# Ariel_v6_2.net
KiCad netlist of a schematic drawn in EAGLE
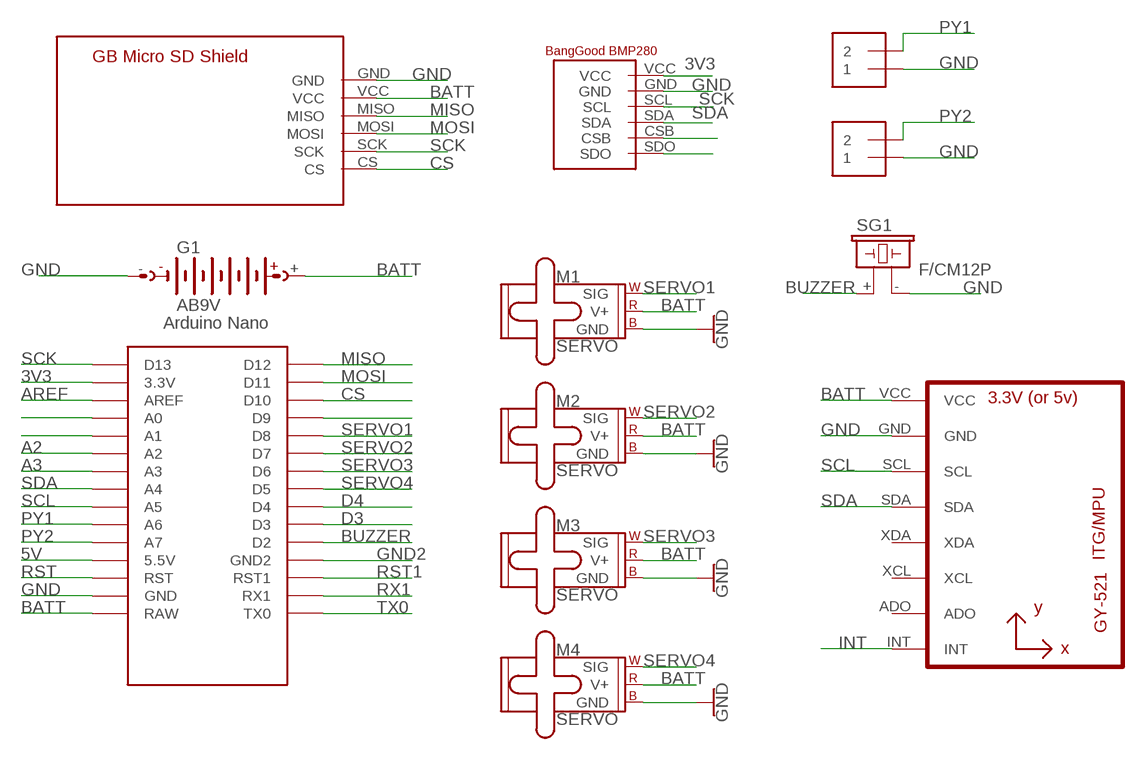
[diagram p0: schematic, sheet 1]

(export (version "E")
  (design (tool "Eeschema 10.0.6"))
  (components
    (comp (ref "G1")
      (value "AB9V")
      (footprint "eagle-import:AB9V")
      (libsource (lib "eagle-import") (part "AB9V"))
    )
    (comp (ref "J1")
      (value "1X2-3.5MM")
      (footprint "eagle-import:1X2-3.5MM")
      (libsource (lib "eagle-import") (part "1X2-3.5MM"))
    )
    (comp (ref "J2")
      (value "1X2-3.5MM")
      (footprint "eagle-import:1X2-3.5MM")
      (libsource (lib "eagle-import") (part "1X2-3.5MM"))
    )
    (comp (ref "M1")
      (value "SERVO")
      (footprint "eagle-import:1X03")
      (libsource (lib "eagle-import") (part "SERVO"))
    )
    (comp (ref "M2")
      (value "SERVO")
      (footprint "eagle-import:1X03")
      (libsource (lib "eagle-import") (part "SERVO"))
    )
    (comp (ref "M3")
      (value "SERVO")
      (footprint "eagle-import:1X03")
      (libsource (lib "eagle-import") (part "SERVO"))
    )
    (comp (ref "M4")
      (value "SERVO")
      (footprint "eagle-import:1X03")
      (libsource (lib "eagle-import") (part "SERVO"))
    )
    (comp (ref "SG1")
      (value "F/CM12P")
      (footprint "eagle-import:F_CM12P")
      (libsource (lib "eagle-import") (part "F/CM12P"))
    )
    (comp (ref "U$1")
      (value "NANO")
      (footprint "eagle-import:NANO")
      (libsource (lib "eagle-import") (part "NANO"))
    )
    (comp (ref "U$2")
      (value "BG_BMP280")
      (footprint "eagle-import:01BG_BMP280")
      (libsource (lib "eagle-import") (part "BG_BMP280"))
    )
    (comp (ref "U$3")
      (value "GBMICROSDSHIELD")
      (footprint "eagle-import:GBMICROSDSHIELD")
      (libsource (lib "eagle-import") (part "GBMICROSDSHIELD"))
    )
    (comp (ref "U1")
      (value "GY-521MPU6050")
      (footprint "eagle-import:GY-521")
      (libsource (lib "eagle-import") (part "GY-521MPU6050"))
    )
  )
  (nets
    (net (code "1") (name "/3V3") (class "Default")
      (node (ref "U$1") (pin "3.3V") (pinfunction "3.3V_3.3V") (pintype "bidirectional"))
      (node (ref "U$2") (pin "VCC") (pinfunction "VCC_VCC") (pintype "bidirectional"))
    )
    (net (code "2") (name "/5V") (class "Default")
      (node (ref "U$1") (pin "5V") (pinfunction "5.5V_5V") (pintype "bidirectional"))
    )
    (net (code "3") (name "/A2") (class "Default")
      (node (ref "U$1") (pin "A2") (pinfunction "A2_A2") (pintype "bidirectional"))
    )
    (net (code "4") (name "/A3") (class "Default")
      (node (ref "U$1") (pin "A3") (pinfunction "A3_A3") (pintype "bidirectional"))
    )
    (net (code "5") (name "/AREF") (class "Default")
      (node (ref "U$1") (pin "AREF") (pinfunction "AREF_AREF") (pintype "bidirectional"))
    )
    (net (code "6") (name "/BATT") (class "Default")
      (node (ref "G1") (pin "+") (pinfunction "+_+") (pintype "passive"))
      (node (ref "M1") (pin "2") (pinfunction "V+_2") (pintype "bidirectional"))
      (node (ref "M2") (pin "2") (pinfunction "V+_2") (pintype "bidirectional"))
      (node (ref "M3") (pin "2") (pinfunction "V+_2") (pintype "bidirectional"))
      (node (ref "M4") (pin "2") (pinfunction "V+_2") (pintype "bidirectional"))
      (node (ref "U$1") (pin "RAW") (pinfunction "RAW_RAW") (pintype "bidirectional"))
      (node (ref "U$3") (pin "VCC") (pinfunction "VCC_VCC") (pintype "bidirectional"))
      (node (ref "U1") (pin "VCC") (pinfunction "VCC_VCC") (pintype "bidirectional"))
    )
    (net (code "7") (name "/BUZZER") (class "Default")
      (node (ref "SG1") (pin "+") (pinfunction "1_+") (pintype "passive"))
      (node (ref "U$1") (pin "D2") (pinfunction "D2_D2") (pintype "bidirectional"))
    )
    (net (code "8") (name "/CS") (class "Default")
      (node (ref "U$1") (pin "D10") (pinfunction "D10_D10") (pintype "bidirectional"))
      (node (ref "U$3") (pin "CS") (pinfunction "CS_CS") (pintype "bidirectional"))
    )
    (net (code "9") (name "/D3") (class "Default")
      (node (ref "U$1") (pin "D3") (pinfunction "D3_D3") (pintype "bidirectional"))
    )
    (net (code "10") (name "/D4") (class "Default")
      (node (ref "U$1") (pin "D4") (pinfunction "D4_D4") (pintype "bidirectional"))
    )
    (net (code "11") (name "/GND2") (class "Default")
      (node (ref "U$1") (pin "GND1") (pinfunction "GND2_GND1") (pintype "bidirectional"))
    )
    (net (code "12") (name "/INT") (class "Default")
      (node (ref "U1") (pin "INT") (pinfunction "INT_INT") (pintype "bidirectional"))
    )
    (net (code "13") (name "/MISO") (class "Default")
      (node (ref "U$1") (pin "D12") (pinfunction "D12_D12") (pintype "bidirectional"))
      (node (ref "U$3") (pin "MISO") (pinfunction "MISO_MISO") (pintype "bidirectional"))
    )
    (net (code "14") (name "/MOSI") (class "Default")
      (node (ref "U$1") (pin "D11") (pinfunction "D11_D11") (pintype "bidirectional"))
      (node (ref "U$3") (pin "MOSI") (pinfunction "MOSI_MOSI") (pintype "bidirectional"))
    )
    (net (code "15") (name "/PY1") (class "Default")
      (node (ref "J1") (pin "2") (pinfunction "2_2") (pintype "passive"))
      (node (ref "U$1") (pin "A6") (pinfunction "A6_A6") (pintype "bidirectional"))
    )
    (net (code "16") (name "/PY2") (class "Default")
      (node (ref "J2") (pin "2") (pinfunction "2_2") (pintype "passive"))
      (node (ref "U$1") (pin "A7") (pinfunction "A7_A7") (pintype "bidirectional"))
    )
    (net (code "17") (name "/RST") (class "Default")
      (node (ref "U$1") (pin "RST") (pinfunction "RST_RST") (pintype "bidirectional"))
    )
    (net (code "18") (name "/RST1") (class "Default")
      (node (ref "U$1") (pin "RST1") (pinfunction "RST1_RST1") (pintype "bidirectional"))
    )
    (net (code "19") (name "/RX1") (class "Default")
      (node (ref "U$1") (pin "RX1") (pinfunction "RX1_RX1") (pintype "bidirectional"))
    )
    (net (code "20") (name "/SCK") (class "Default")
      (node (ref "U$1") (pin "D13") (pinfunction "D13_D13") (pintype "bidirectional"))
      (node (ref "U$2") (pin "SCL") (pinfunction "SCL_SCL") (pintype "bidirectional"))
      (node (ref "U$3") (pin "SCK") (pinfunction "SCK_SCK") (pintype "bidirectional"))
    )
    (net (code "21") (name "/SCL") (class "Default")
      (node (ref "U$1") (pin "A5") (pinfunction "A5_A5") (pintype "bidirectional"))
      (node (ref "U1") (pin "SCL") (pinfunction "SCL_SCL") (pintype "bidirectional"))
    )
    (net (code "22") (name "/SDA") (class "Default")
      (node (ref "U$1") (pin "A4") (pinfunction "A4_A4") (pintype "bidirectional"))
      (node (ref "U$2") (pin "SDA") (pinfunction "SDA_SDA") (pintype "bidirectional"))
      (node (ref "U1") (pin "SDA") (pinfunction "SDA_SDA") (pintype "bidirectional"))
    )
    (net (code "23") (name "/SERVO1") (class "Default")
      (node (ref "M1") (pin "1") (pinfunction "SIG_1") (pintype "bidirectional"))
      (node (ref "U$1") (pin "D8") (pinfunction "D8_D8") (pintype "bidirectional"))
    )
    (net (code "24") (name "/SERVO2") (class "Default")
      (node (ref "M2") (pin "1") (pinfunction "SIG_1") (pintype "bidirectional"))
      (node (ref "U$1") (pin "D7") (pinfunction "D7_D7") (pintype "bidirectional"))
    )
    (net (code "25") (name "/SERVO3") (class "Default")
      (node (ref "M3") (pin "1") (pinfunction "SIG_1") (pintype "bidirectional"))
      (node (ref "U$1") (pin "D6") (pinfunction "D6_D6") (pintype "bidirectional"))
    )
    (net (code "26") (name "/SERVO4") (class "Default")
      (node (ref "M4") (pin "1") (pinfunction "SIG_1") (pintype "bidirectional"))
      (node (ref "U$1") (pin "D5") (pinfunction "D5_D5") (pintype "bidirectional"))
    )
    (net (code "27") (name "/TX0") (class "Default")
      (node (ref "U$1") (pin "TX0") (pinfunction "TX0_TX0") (pintype "bidirectional"))
    )
    (net (code "28") (name "GND") (class "Default")
      (node (ref "G1") (pin "-") (pinfunction "-_-") (pintype "passive"))
      (node (ref "J1") (pin "1") (pinfunction "1_1") (pintype "passive"))
      (node (ref "J2") (pin "1") (pinfunction "1_1") (pintype "passive"))
      (node (ref "M1") (pin "3") (pinfunction "GND_3") (pintype "bidirectional"))
      (node (ref "M2") (pin "3") (pinfunction "GND_3") (pintype "bidirectional"))
      (node (ref "M3") (pin "3") (pinfunction "GND_3") (pintype "bidirectional"))
      (node (ref "M4") (pin "3") (pinfunction "GND_3") (pintype "bidirectional"))
      (node (ref "SG1") (pin "-") (pinfunction "2_-") (pintype "passive"))
      (node (ref "U$1") (pin "GND") (pinfunction "GND_GND") (pintype "bidirectional"))
      (node (ref "U$2") (pin "GND") (pinfunction "GND_GND") (pintype "bidirectional"))
      (node (ref "U$3") (pin "GND") (pinfunction "GND_GND") (pintype "bidirectional"))
      (node (ref "U1") (pin "GND") (pinfunction "GND_GND") (pintype "bidirectional"))
    )
    (net (code "29") (name "unconnected-(U$1-PadA0)") (class "Default")
      (node (ref "U$1") (pin "A0") (pinfunction "A0_A0") (pintype "bidirectional"))
    )
    (net (code "30") (name "unconnected-(U$1-PadA1)") (class "Default")
      (node (ref "U$1") (pin "A1") (pinfunction "A1_A1") (pintype "bidirectional"))
    )
    (net (code "31") (name "unconnected-(U$1-PadD9)") (class "Default")
      (node (ref "U$1") (pin "D9") (pinfunction "D9_D9") (pintype "bidirectional"))
    )
    (net (code "32") (name "unconnected-(U$1-PadICSP1)") (class "Default")
      (node (ref "U$1") (pin "ICSP1") (pinfunction "ICSP1_ICSP1") (pintype "bidirectional"))
    )
    (net (code "33") (name "unconnected-(U$1-PadICSP2)") (class "Default")
      (node (ref "U$1") (pin "ICSP2") (pinfunction "ICSP2_ICSP2") (pintype "bidirectional"))
    )
    (net (code "34") (name "unconnected-(U$1-PadICSP3)") (class "Default")
      (node (ref "U$1") (pin "ICSP3") (pinfunction "ICSP3_ICSP3") (pintype "bidirectional"))
    )
    (net (code "35") (name "unconnected-(U$1-PadICSP4)") (class "Default")
      (node (ref "U$1") (pin "ICSP4") (pinfunction "ICSP4_ICSP4") (pintype "bidirectional"))
    )
    (net (code "36") (name "unconnected-(U$1-PadICSP5)") (class "Default")
      (node (ref "U$1") (pin "ICSP5") (pinfunction "ICSP5_ICSP5") (pintype "bidirectional"))
    )
    (net (code "37") (name "unconnected-(U$1-PadICSP6)") (class "Default")
      (node (ref "U$1") (pin "ICSP6") (pinfunction "ICSP6_ICSP6") (pintype "bidirectional"))
    )
    (net (code "38") (name "unconnected-(U$2-PadCSB)") (class "Default")
      (node (ref "U$2") (pin "CSB") (pinfunction "CSB_CSB") (pintype "bidirectional"))
    )
    (net (code "39") (name "unconnected-(U$2-PadSDO)") (class "Default")
      (node (ref "U$2") (pin "SDO") (pinfunction "SDO_SDO") (pintype "bidirectional"))
    )
    (net (code "40") (name "unconnected-(U1-PadADO)") (class "Default")
      (node (ref "U1") (pin "ADO") (pinfunction "ADO_ADO") (pintype "bidirectional"))
    )
    (net (code "41") (name "unconnected-(U1-PadXCL)") (class "Default")
      (node (ref "U1") (pin "XCL") (pinfunction "XCL_XCL") (pintype "bidirectional"))
    )
    (net (code "42") (name "unconnected-(U1-PadXDA)") (class "Default")
      (node (ref "U1") (pin "XDA") (pinfunction "XDA_XDA") (pintype "bidirectional"))
    )
  )
)
